# dual-voltage.net
KiCad netlist of a schematic drawn in EAGLE
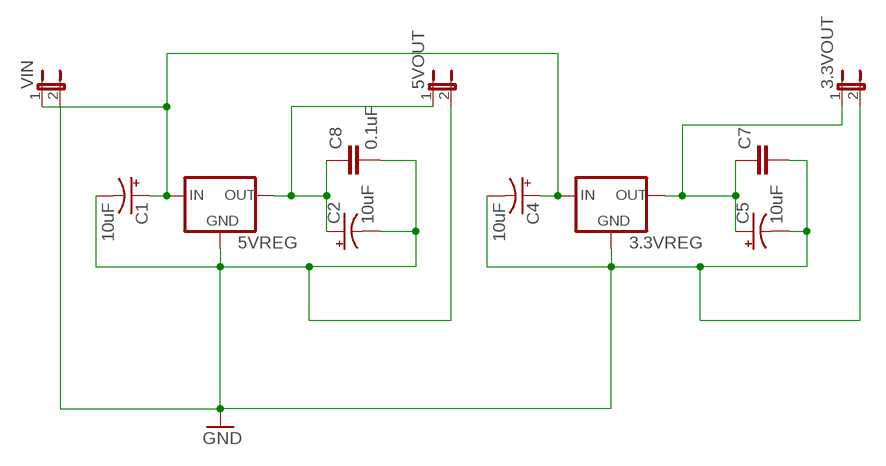
[diagram p0: schematic, sheet 1]

(export (version "E")
  (design (tool "Eeschema 10.0.6"))
  (components
    (comp (ref "3.3VOUT")
      (value "JUMPER-2PTH")
      (footprint "eagle-import:1X02")
      (libsource (lib "eagle-import") (part "JUMPER-2PTH"))
    )
    (comp (ref "3.3VREG")
      (value "78XXS")
      (footprint "eagle-import:78XXS")
      (libsource (lib "eagle-import") (part "78XXS"))
    )
    (comp (ref "5VOUT")
      (value "JUMPER-2PTH")
      (footprint "eagle-import:1X02")
      (libsource (lib "eagle-import") (part "JUMPER-2PTH"))
    )
    (comp (ref "5VREG")
      (value "78XXS")
      (footprint "eagle-import:78XXS")
      (libsource (lib "eagle-import") (part "78XXS"))
    )
    (comp (ref "C1")
      (value "10uF")
      (footprint "eagle-import:CPOL-RADIAL-10UF-25V")
      (libsource (lib "eagle-import") (part "CAP_POLPTH2"))
    )
    (comp (ref "C2")
      (value "10uF")
      (footprint "eagle-import:CPOL-RADIAL-10UF-25V")
      (libsource (lib "eagle-import") (part "CAP_POLPTH2"))
    )
    (comp (ref "C4")
      (value "10uF")
      (footprint "eagle-import:CPOL-RADIAL-10UF-25V")
      (libsource (lib "eagle-import") (part "CAP_POLPTH2"))
    )
    (comp (ref "C5")
      (value "10uF")
      (footprint "eagle-import:CPOL-RADIAL-10UF-25V")
      (libsource (lib "eagle-import") (part "CAP_POLPTH2"))
    )
    (comp (ref "C7")
      (value "CAPPTH2")
      (footprint "eagle-import:CAP-PTH-SMALL2")
      (libsource (lib "eagle-import") (part "CAPPTH2"))
    )
    (comp (ref "C8")
      (value "0.1uF")
      (footprint "eagle-import:CAP-PTH-SMALL2")
      (libsource (lib "eagle-import") (part "CAPPTH2"))
    )
    (comp (ref "VIN")
      (value "JUMPER-2PTH")
      (footprint "eagle-import:1X02")
      (libsource (lib "eagle-import") (part "JUMPER-2PTH"))
    )
  )
  (nets
    (net (code "1") (name "GND") (class "Default")
      (node (ref "3.3VOUT") (pin "2") (pinfunction "2_2") (pintype "passive"))
      (node (ref "3.3VREG") (pin "GND") (pinfunction "GND_GND") (pintype "input"))
      (node (ref "5VOUT") (pin "2") (pinfunction "2_2") (pintype "passive"))
      (node (ref "5VREG") (pin "GND") (pinfunction "GND_GND") (pintype "input"))
      (node (ref "C1") (pin "2") (pinfunction "-_2") (pintype "passive"))
      (node (ref "C2") (pin "2") (pinfunction "-_2") (pintype "passive"))
      (node (ref "C4") (pin "2") (pinfunction "-_2") (pintype "passive"))
      (node (ref "C5") (pin "2") (pinfunction "-_2") (pintype "passive"))
      (node (ref "C7") (pin "2") (pinfunction "2_2") (pintype "passive"))
      (node (ref "C8") (pin "2") (pinfunction "2_2") (pintype "passive"))
      (node (ref "VIN") (pin "2") (pinfunction "2_2") (pintype "passive"))
    )
    (net (code "2") (name "Net-(C1-+)") (class "Default")
      (node (ref "3.3VREG") (pin "IN") (pinfunction "IN_IN") (pintype "input"))
      (node (ref "5VREG") (pin "IN") (pinfunction "IN_IN") (pintype "input"))
      (node (ref "C1") (pin "1") (pinfunction "+_1") (pintype "passive"))
      (node (ref "C4") (pin "1") (pinfunction "+_1") (pintype "passive"))
      (node (ref "VIN") (pin "1") (pinfunction "1_1") (pintype "passive"))
    )
    (net (code "3") (name "Net-(C2-+)") (class "Default")
      (node (ref "5VOUT") (pin "1") (pinfunction "1_1") (pintype "passive"))
      (node (ref "5VREG") (pin "OUT") (pinfunction "OUT_OUT") (pintype "passive"))
      (node (ref "C2") (pin "1") (pinfunction "+_1") (pintype "passive"))
      (node (ref "C8") (pin "1") (pinfunction "1_1") (pintype "passive"))
    )
    (net (code "4") (name "Net-(C5-+)") (class "Default")
      (node (ref "3.3VOUT") (pin "1") (pinfunction "1_1") (pintype "passive"))
      (node (ref "3.3VREG") (pin "OUT") (pinfunction "OUT_OUT") (pintype "passive"))
      (node (ref "C5") (pin "1") (pinfunction "+_1") (pintype "passive"))
      (node (ref "C7") (pin "1") (pinfunction "1_1") (pintype "passive"))
    )
  )
)
